# Sheet5_LCD.net
KiCad netlist of a schematic drawn in Altium Designer
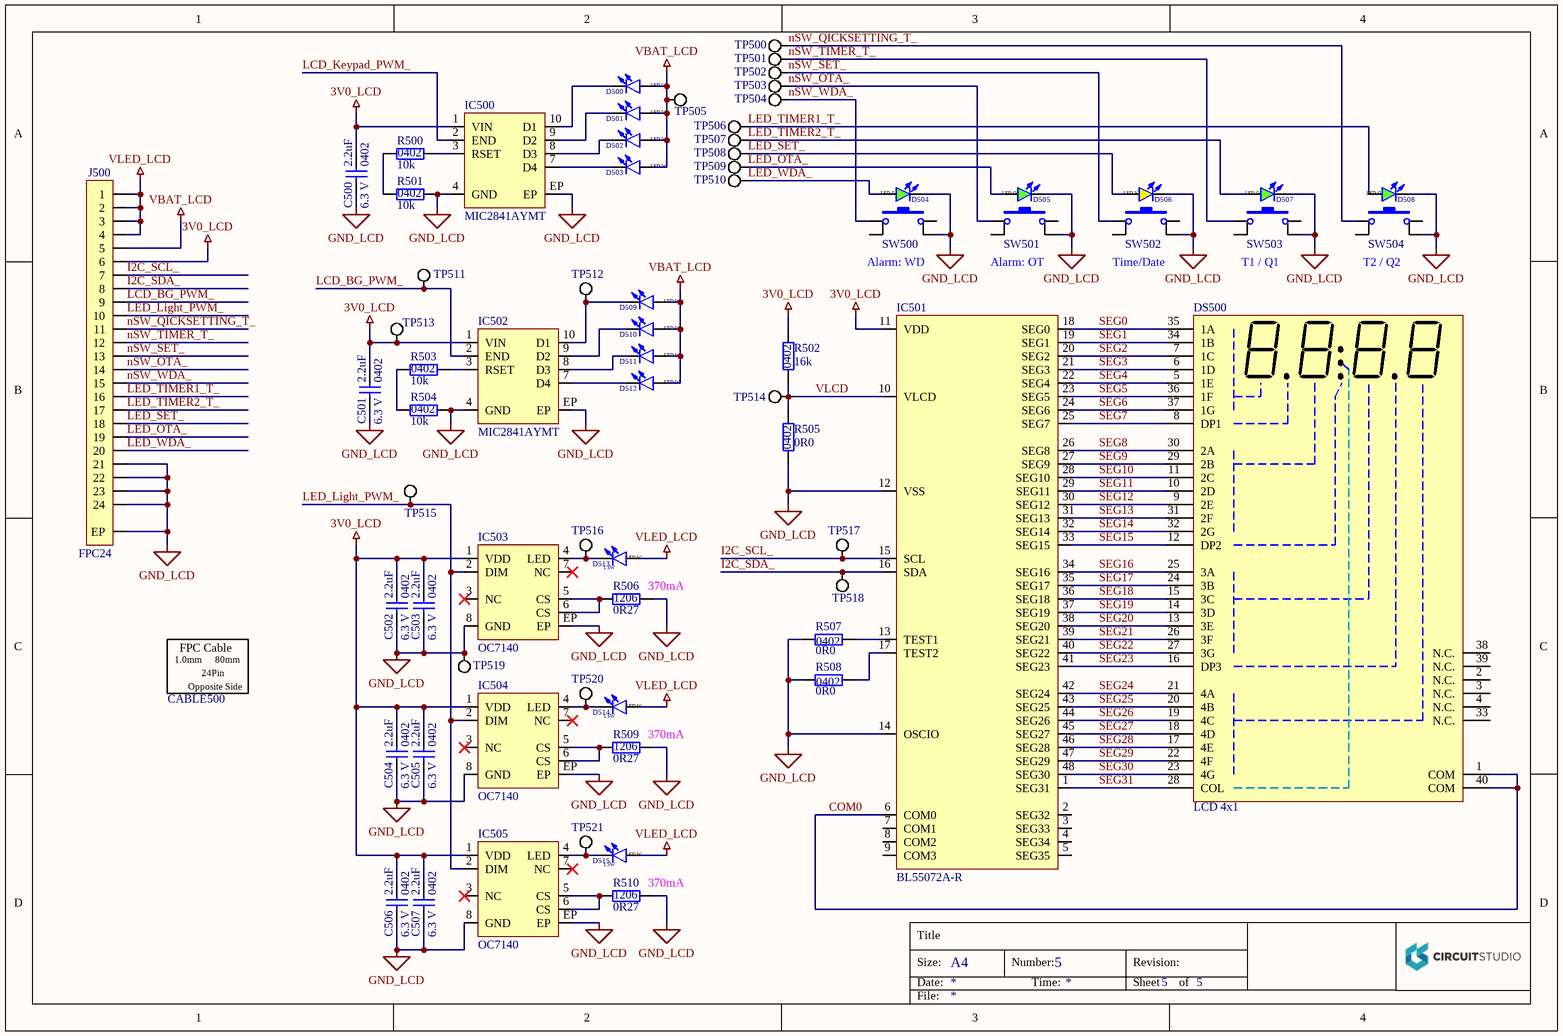
[diagram p0: Sheet5_LCD.SchDoc]

(export (version "E")
  (design (tool "Eeschema 10.0.6"))
  (components
    (comp (ref "C500")
      (value "C 2.2uF 0402 6.3V")
      (footprint "0402")
      (description "CAP CER 2.2UF 6.3V X6T 0402")
      (fields
        (field (name "MANUFACTURER") "Murata Electronics")
        (field (name "MANUFACTURER PART NUMBER") "GRM155D80J225ME95D")
        (field (name "CAPACITANCE") "2.2uF")
        (field (name "VOLTAGE") "6.3 V")
      )
      (libsource (lib "CS_Part_Library") (part "CAP_2.2uF_6V3_0402"))
    )
    (comp (ref "C501")
      (value "C 2.2uF 0402 6.3V")
      (footprint "0402")
      (description "CAP CER 2.2UF 6.3V X6T 0402")
      (fields
        (field (name "MANUFACTURER") "Murata Electronics")
        (field (name "MANUFACTURER PART NUMBER") "GRM155D80J225ME95D")
        (field (name "CAPACITANCE") "2.2uF")
        (field (name "VOLTAGE") "6.3 V")
      )
      (libsource (lib "CS_Part_Library") (part "CAP_2.2uF_6V3_0402"))
    )
    (comp (ref "C502")
      (value "C 2.2uF 0402 6.3V")
      (footprint "0402")
      (description "CAP CER 2.2UF 6.3V X6T 0402")
      (fields
        (field (name "MANUFACTURER") "Murata Electronics")
        (field (name "MANUFACTURER PART NUMBER") "GRM155D80J225ME95D")
        (field (name "CAPACITANCE") "2.2uF")
        (field (name "VOLTAGE") "6.3 V")
      )
      (libsource (lib "CS_Part_Library") (part "CAP_2.2uF_6V3_0402"))
    )
    (comp (ref "C503")
      (value "C 2.2uF 0402 6.3V")
      (footprint "0402")
      (description "CAP CER 2.2UF 6.3V X6T 0402")
      (fields
        (field (name "MANUFACTURER") "Murata Electronics")
        (field (name "MANUFACTURER PART NUMBER") "GRM155D80J225ME95D")
        (field (name "CAPACITANCE") "2.2uF")
        (field (name "VOLTAGE") "6.3 V")
      )
      (libsource (lib "CS_Part_Library") (part "CAP_2.2uF_6V3_0402"))
    )
    (comp (ref "C504")
      (value "C 2.2uF 0402 6.3V")
      (footprint "0402")
      (description "CAP CER 2.2UF 6.3V X6T 0402")
      (fields
        (field (name "MANUFACTURER") "Murata Electronics")
        (field (name "MANUFACTURER PART NUMBER") "GRM155D80J225ME95D")
        (field (name "CAPACITANCE") "2.2uF")
        (field (name "VOLTAGE") "6.3 V")
      )
      (libsource (lib "CS_Part_Library") (part "CAP_2.2uF_6V3_0402"))
    )
    (comp (ref "C505")
      (value "C 2.2uF 0402 6.3V")
      (footprint "0402")
      (description "CAP CER 2.2UF 6.3V X6T 0402")
      (fields
        (field (name "MANUFACTURER") "Murata Electronics")
        (field (name "MANUFACTURER PART NUMBER") "GRM155D80J225ME95D")
        (field (name "CAPACITANCE") "2.2uF")
        (field (name "VOLTAGE") "6.3 V")
      )
      (libsource (lib "CS_Part_Library") (part "CAP_2.2uF_6V3_0402"))
    )
    (comp (ref "C506")
      (value "C 2.2uF 0402 6.3V")
      (footprint "0402")
      (description "CAP CER 2.2UF 6.3V X6T 0402")
      (fields
        (field (name "MANUFACTURER") "Murata Electronics")
        (field (name "MANUFACTURER PART NUMBER") "GRM155D80J225ME95D")
        (field (name "CAPACITANCE") "2.2uF")
        (field (name "VOLTAGE") "6.3 V")
      )
      (libsource (lib "CS_Part_Library") (part "CAP_2.2uF_6V3_0402"))
    )
    (comp (ref "C507")
      (value "C 2.2uF 0402 6.3V")
      (footprint "0402")
      (description "CAP CER 2.2UF 6.3V X6T 0402")
      (fields
        (field (name "MANUFACTURER") "Murata Electronics")
        (field (name "MANUFACTURER PART NUMBER") "GRM155D80J225ME95D")
        (field (name "CAPACITANCE") "2.2uF")
        (field (name "VOLTAGE") "6.3 V")
      )
      (libsource (lib "CS_Part_Library") (part "CAP_2.2uF_6V3_0402"))
    )
    (comp (ref "CABLE500")
      (value "FPC24p80mm")
      (description "FPC Cable 1mm Pitch 24Pin 80mm Opposite Sides")
      (fields
        (field (name "MANUFACTURER") "LX")
        (field (name "MANUFACTURER PART NUMBER") "C50299")
        (field (name "PITCH") "1.0mm")
        (field (name "LENGTH") "80mm")
        (field (name "MODE") "Opposite Side")
        (field (name "NOOFPINS") "24Pin")
      )
      (libsource (lib "Symbols") (part "CABLE_FPC24_80"))
    )
    (comp (ref "D500")
      (value "LED W")
      (footprint "LED_99-218UMC_side")
      (description "LED WHITE SIDE SMD")
      (fields
        (field (name "MANUFACTURER") "Everlight Elec")
        (field (name "MANUFACTURER PART NUMBER") "99-218UMC/1637CD/TR8-T")
      )
      (libsource (lib "Symbols") (part "D_LED_White_s"))
    )
    (comp (ref "D501")
      (value "LED W")
      (footprint "LED_99-218UMC_side")
      (description "LED WHITE SIDE SMD")
      (fields
        (field (name "MANUFACTURER") "Everlight Elec")
        (field (name "MANUFACTURER PART NUMBER") "99-218UMC/1637CD/TR8-T")
      )
      (libsource (lib "Symbols") (part "D_LED_White_s"))
    )
    (comp (ref "D502")
      (value "LED W")
      (footprint "LED_99-218UMC_side")
      (description "LED WHITE SIDE SMD")
      (fields
        (field (name "MANUFACTURER") "Everlight Elec")
        (field (name "MANUFACTURER PART NUMBER") "99-218UMC/1637CD/TR8-T")
      )
      (libsource (lib "Symbols") (part "D_LED_White_s"))
    )
    (comp (ref "D503")
      (value "LED W")
      (footprint "LED_99-218UMC_side")
      (description "LED WHITE SIDE SMD")
      (fields
        (field (name "MANUFACTURER") "Everlight Elec")
        (field (name "MANUFACTURER PART NUMBER") "99-218UMC/1637CD/TR8-T")
      )
      (libsource (lib "Symbols") (part "D_LED_White_s"))
    )
    (comp (ref "D504")
      (value "LED G")
      (footprint "LED_0603")
      (description "LED GREEN DIFFUSED 0603 SMD")
      (fields
        (field (name "MANUFACTURER") "OSRAM Opto Semiconductors Inc.")
        (field (name "MANUFACTURER PART NUMBER") "LT Q39G-Q1OO-25-1")
      )
      (libsource (lib "CS_Part_Library") (part "D_LED_Green_0603"))
    )
    (comp (ref "D505")
      (value "LED G")
      (footprint "LED_0603")
      (description "LED GREEN DIFFUSED 0603 SMD")
      (fields
        (field (name "MANUFACTURER") "OSRAM Opto Semiconductors Inc.")
        (field (name "MANUFACTURER PART NUMBER") "LT Q39G-Q1OO-25-1")
      )
      (libsource (lib "CS_Part_Library") (part "D_LED_Green_0603"))
    )
    (comp (ref "D506")
      (value "LED Y")
      (footprint "LED_0603")
      (description "LED YELLOW DIFFUSED")
      (fields
        (field (name "MANUFACTURER") "Stanley Electric Co")
        (field (name "MANUFACTURER PART NUMBER") "FKY1111C-TR")
      )
      (libsource (lib "CS_Part_Library") (part "D_LED_Yellow_0603"))
    )
    (comp (ref "D507")
      (value "LED G")
      (footprint "LED_0603")
      (description "LED GREEN DIFFUSED 0603 SMD")
      (fields
        (field (name "MANUFACTURER") "OSRAM Opto Semiconductors Inc.")
        (field (name "MANUFACTURER PART NUMBER") "LT Q39G-Q1OO-25-1")
      )
      (libsource (lib "CS_Part_Library") (part "D_LED_Green_0603"))
    )
    (comp (ref "D508")
      (value "LED G")
      (footprint "LED_0603")
      (description "LED GREEN DIFFUSED 0603 SMD")
      (fields
        (field (name "MANUFACTURER") "OSRAM Opto Semiconductors Inc.")
        (field (name "MANUFACTURER PART NUMBER") "LT Q39G-Q1OO-25-1")
      )
      (libsource (lib "CS_Part_Library") (part "D_LED_Green_0603"))
    )
    (comp (ref "D509")
      (value "LED W")
      (footprint "LED_99-218UMC_side")
      (description "LED WHITE SIDE SMD")
      (fields
        (field (name "MANUFACTURER") "Everlight Elec")
        (field (name "MANUFACTURER PART NUMBER") "99-218UMC/1637CD/TR8-T")
      )
      (libsource (lib "Symbols") (part "D_LED_White_s"))
    )
    (comp (ref "D510")
      (value "LED W")
      (footprint "LED_99-218UMC_side")
      (description "LED WHITE SIDE SMD")
      (fields
        (field (name "MANUFACTURER") "Everlight Elec")
        (field (name "MANUFACTURER PART NUMBER") "99-218UMC/1637CD/TR8-T")
      )
      (libsource (lib "Symbols") (part "D_LED_White_s"))
    )
    (comp (ref "D511")
      (value "LED W")
      (footprint "LED_99-218UMC_side")
      (description "LED WHITE SIDE SMD")
      (fields
        (field (name "MANUFACTURER") "Everlight Elec")
        (field (name "MANUFACTURER PART NUMBER") "99-218UMC/1637CD/TR8-T")
      )
      (libsource (lib "Symbols") (part "D_LED_White_s"))
    )
    (comp (ref "D512")
      (value "LED W")
      (footprint "LED_99-218UMC_side")
      (description "LED WHITE SIDE SMD")
      (fields
        (field (name "MANUFACTURER") "Everlight Elec")
        (field (name "MANUFACTURER PART NUMBER") "99-218UMC/1637CD/TR8-T")
      )
      (libsource (lib "Symbols") (part "D_LED_White_s"))
    )
    (comp (ref "D513")
      (value "LED W")
      (footprint "LED_3.5x3.15")
      (description "LED XLAMP WARM WHITE 3250K 4SMD")
      (fields
        (field (name "MANUFACTURER") "CreeLED, Inc.")
        (field (name "MANUFACTURER PART NUMBER") "MLEAWT-A1-0000-0003F7")
        (field (name "POWER") "1.5W")
      )
      (libsource (lib "CS_Part_Library") (part "D_LED_W_HP"))
    )
    (comp (ref "D514")
      (value "LED W")
      (footprint "LED_3.5x3.15")
      (description "LED XLAMP WARM WHITE 3250K 4SMD")
      (fields
        (field (name "MANUFACTURER") "CreeLED, Inc.")
        (field (name "MANUFACTURER PART NUMBER") "MLEAWT-A1-0000-0003F7")
        (field (name "POWER") "1.5W")
      )
      (libsource (lib "CS_Part_Library") (part "D_LED_W_HP"))
    )
    (comp (ref "D515")
      (value "LED W")
      (footprint "LED_3.5x3.15")
      (description "LED XLAMP WARM WHITE 3250K 4SMD")
      (fields
        (field (name "MANUFACTURER") "CreeLED, Inc.")
        (field (name "MANUFACTURER PART NUMBER") "MLEAWT-A1-0000-0003F7")
        (field (name "POWER") "1.5W")
      )
      (libsource (lib "CS_Part_Library") (part "D_LED_W_HP"))
    )
    (comp (ref "DS500")
      (value "LCD 4x1")
      (footprint "DISPL_7SEG_4")
      (description "LCD MOD 4 DIG 4 X 1 REFLECTIVE")
      (fields
        (field (name "MANUFACTURER") "Varitronix")
        (field (name "MANUFACTURER PART NUMBER") "VI-402-DP-RC-S")
      )
      (libsource (lib "Symbols") (part "DISPL_7SEG_4x1"))
    )
    (comp (ref "IC500")
      (value "MIC2841AYMT")
      (footprint "UFDFN-10")
      (description "IC LED DRIVER 4 CH")
      (fields
        (field (name "MANUFACTURER") "Microchip Technology")
        (field (name "MANUFACTURER PART NUMBER") "MIC2841AYMT-TR")
      )
      (libsource (lib "CS_Part_Library") (part "IC_LED_cntr_MIC2841"))
    )
    (comp (ref "IC501")
      (value "BL55072A-R")
      (footprint "TSSOP-48")
      (description "IC LCD DRIVER 36SEG TSSOP-48")
      (fields (field (name "MANUFACTURER") "BL(Shanghai Belling)"))
      (libsource (lib "Symbols") (part "IC_LCD_cntr_BL55072A-R"))
    )
    (comp (ref "IC502")
      (value "MIC2841AYMT")
      (footprint "UFDFN-10")
      (description "IC LED DRIVER 4 CH")
      (fields
        (field (name "MANUFACTURER") "Microchip Technology")
        (field (name "MANUFACTURER PART NUMBER") "MIC2841AYMT-TR")
      )
      (libsource (lib "CS_Part_Library") (part "IC_LED_cntr_MIC2841"))
    )
    (comp (ref "IC503")
      (value "OC7140")
      (footprint "SOIC-8-EP")
      (description "IC LED DRIVER 1 CH 2A ESOP8")
      (fields (field (name "MANUFACTURER") "OCX"))
      (libsource (lib "Symbols") (part "IC_LED_cntr_OC7140"))
    )
    (comp (ref "IC504")
      (value "OC7140")
      (footprint "SOIC-8-EP")
      (description "IC LED DRIVER 1 CH 2A ESOP8")
      (fields (field (name "MANUFACTURER") "OCX"))
      (libsource (lib "Symbols") (part "IC_LED_cntr_OC7140"))
    )
    (comp (ref "IC505")
      (value "OC7140")
      (footprint "SOIC-8-EP")
      (description "IC LED DRIVER 1 CH 2A ESOP8")
      (fields (field (name "MANUFACTURER") "OCX"))
      (libsource (lib "Symbols") (part "IC_LED_cntr_OC7140"))
    )
    (comp (ref "J500")
      (value "FPC24")
      (footprint "J_FPC_522712479")
      (description "CONN FPC BOT 24 PIN 1mm Pitch")
      (fields (field (name "MANUFACTURER") "MOLEX") (field (name "MANUFACTURER PART NUMBER") "522712479"))
      (libsource (lib "Symbols") (part "J_FPC24_DS"))
    )
    (comp (ref "R500")
      (value "R 10k 0402")
      (footprint "0402")
      (description "RES 10K OHM 1% 1/16W 0402")
      (fields
        (field (name "MANUFACTURER") "YAGEO")
        (field (name "MANUFACTURER PART NUMBER") "RC0402FR-0710KL")
        (field (name "RESISTANCE") "10k")
      )
      (libsource (lib "CS_Part_Library") (part "R_10k_0402"))
    )
    (comp (ref "R501")
      (value "R 10k 0402")
      (footprint "0402")
      (description "RES 10K OHM 1% 1/16W 0402")
      (fields
        (field (name "MANUFACTURER") "YAGEO")
        (field (name "MANUFACTURER PART NUMBER") "RC0402FR-0710KL")
        (field (name "RESISTANCE") "10k")
      )
      (libsource (lib "CS_Part_Library") (part "R_10k_0402"))
    )
    (comp (ref "R502")
      (value "R 16k 0402")
      (footprint "0402")
      (description "RES 16K OHM 1% 1/16W 0402")
      (fields
        (field (name "MANUFACTURER") "Stackpole Electronics Inc")
        (field (name "MANUFACTURER PART NUMBER") "RMCF0402FT16K0")
        (field (name "RESISTANCE") "16k")
      )
      (libsource (lib "CS_Part_Library") (part "R_16k_0402"))
    )
    (comp (ref "R503")
      (value "R 10k 0402")
      (footprint "0402")
      (description "RES 10K OHM 1% 1/16W 0402")
      (fields
        (field (name "MANUFACTURER") "YAGEO")
        (field (name "MANUFACTURER PART NUMBER") "RC0402FR-0710KL")
        (field (name "RESISTANCE") "10k")
      )
      (libsource (lib "CS_Part_Library") (part "R_10k_0402"))
    )
    (comp (ref "R504")
      (value "R 10k 0402")
      (footprint "0402")
      (description "RES 10K OHM 1% 1/16W 0402")
      (fields
        (field (name "MANUFACTURER") "YAGEO")
        (field (name "MANUFACTURER PART NUMBER") "RC0402FR-0710KL")
        (field (name "RESISTANCE") "10k")
      )
      (libsource (lib "CS_Part_Library") (part "R_10k_0402"))
    )
    (comp (ref "R505")
      (value "R 0R0 0402")
      (footprint "0402")
      (description "RES 0 OHM JUMPER 1/16W 0402")
      (fields
        (field (name "MANUFACTURER") "Stackpole Electronics Inc")
        (field (name "MANUFACTURER PART NUMBER") "RMCF0402ZT0R00")
        (field (name "RESISTANCE") "0R0")
      )
      (libsource (lib "") (part "R_0R0_0402_1"))
    )
    (comp (ref "R506")
      (value "R 0R27 1206")
      (footprint "1206")
      (description "RES 0.27 OHM 1% 1/3W 1206")
      (fields
        (field (name "MANUFACTURER") "RALEC")
        (field (name "MANUFACTURER PART NUMBER") "RTT06R270FTP")
        (field (name "RESISTANCE") "0R27")
      )
      (libsource (lib "Symbols") (part "R_0R27_1206"))
    )
    (comp (ref "R507")
      (value "R 0R0 0402")
      (footprint "0402")
      (description "RES 0 OHM JUMPER 1/16W 0402")
      (fields
        (field (name "MANUFACTURER") "Stackpole Electronics Inc")
        (field (name "MANUFACTURER PART NUMBER") "RMCF0402ZT0R00")
        (field (name "RESISTANCE") "0R0")
      )
      (libsource (lib "CS_Part_Library") (part "R_0R0_0402"))
    )
    (comp (ref "R508")
      (value "R 0R0 0402")
      (footprint "0402")
      (description "RES 0 OHM JUMPER 1/16W 0402")
      (fields
        (field (name "MANUFACTURER") "Stackpole Electronics Inc")
        (field (name "MANUFACTURER PART NUMBER") "RMCF0402ZT0R00")
        (field (name "RESISTANCE") "0R0")
      )
      (libsource (lib "CS_Part_Library") (part "R_0R0_0402"))
    )
    (comp (ref "R509")
      (value "R 0R27 1206")
      (footprint "1206")
      (description "RES 0.27 OHM 1% 1/3W 1206")
      (fields
        (field (name "MANUFACTURER") "RALEC")
        (field (name "MANUFACTURER PART NUMBER") "RTT06R270FTP")
        (field (name "RESISTANCE") "0R27")
      )
      (libsource (lib "Symbols") (part "R_0R27_1206"))
    )
    (comp (ref "R510")
      (value "R 0R27 1206")
      (footprint "1206")
      (description "RES 0.27 OHM 1% 1/3W 1206")
      (fields
        (field (name "MANUFACTURER") "RALEC")
        (field (name "MANUFACTURER PART NUMBER") "RTT06R270FTP")
        (field (name "RESISTANCE") "0R27")
      )
      (libsource (lib "Symbols") (part "R_0R27_1206"))
    )
    (comp (ref "SW500")
      (value "SW")
      (footprint "SW_BRIGHT_6.1x6.1")
      (description "SWITCH TACTILE SW-SMD")
      (fields
        (field (name "MANUFACTURER") "BRIGHT")
        (field (name "MANUFACTURER PART NUMBER") "TSA063G50-250")
      )
      (libsource (lib "CS_Part_Library") (part "SW_TactileSW_V_2"))
    )
    (comp (ref "SW501")
      (value "SW")
      (footprint "SW_BRIGHT_6.1x6.1")
      (description "SWITCH TACTILE SW-SMD")
      (fields
        (field (name "MANUFACTURER") "BRIGHT")
        (field (name "MANUFACTURER PART NUMBER") "TSA063G50-250")
      )
      (libsource (lib "CS_Part_Library") (part "SW_TactileSW_V_2"))
    )
    (comp (ref "SW502")
      (value "SW")
      (footprint "SW_BRIGHT_6.1x6.1")
      (description "SWITCH TACTILE SW-SMD")
      (fields
        (field (name "MANUFACTURER") "BRIGHT")
        (field (name "MANUFACTURER PART NUMBER") "TSA063G50-250")
      )
      (libsource (lib "CS_Part_Library") (part "SW_TactileSW_V_2"))
    )
    (comp (ref "SW503")
      (value "SW")
      (footprint "SW_BRIGHT_6.1x6.1")
      (description "SWITCH TACTILE SW-SMD")
      (fields
        (field (name "MANUFACTURER") "BRIGHT")
        (field (name "MANUFACTURER PART NUMBER") "TSA063G50-250")
      )
      (libsource (lib "CS_Part_Library") (part "SW_TactileSW_V_2"))
    )
    (comp (ref "SW504")
      (value "SW")
      (footprint "SW_BRIGHT_6.1x6.1")
      (description "SWITCH TACTILE SW-SMD")
      (fields
        (field (name "MANUFACTURER") "BRIGHT")
        (field (name "MANUFACTURER PART NUMBER") "TSA063G50-250")
      )
      (libsource (lib "CS_Part_Library") (part "SW_TactileSW_V_2"))
    )
    (comp (ref "TP500")
      (value "TP")
      (footprint "TP_1mm")
      (description "Test Point 1mm")
      (libsource (lib "CS_Part_Library") (part "TP_1mm"))
    )
    (comp (ref "TP501")
      (value "TP")
      (footprint "TP_1mm")
      (description "Test Point 1mm")
      (libsource (lib "CS_Part_Library") (part "TP_1mm"))
    )
    (comp (ref "TP502")
      (value "TP")
      (footprint "TP_1mm")
      (description "Test Point 1mm")
      (libsource (lib "CS_Part_Library") (part "TP_1mm"))
    )
    (comp (ref "TP503")
      (value "TP")
      (footprint "TP_1mm")
      (description "Test Point 1mm")
      (libsource (lib "CS_Part_Library") (part "TP_1mm"))
    )
    (comp (ref "TP504")
      (value "TP")
      (footprint "TP_1mm")
      (description "Test Point 1mm")
      (libsource (lib "CS_Part_Library") (part "TP_1mm"))
    )
    (comp (ref "TP505")
      (value "TP")
      (footprint "TP_1mm")
      (description "Test Point 1mm")
      (libsource (lib "CS_Part_Library") (part "TP_1mm"))
    )
    (comp (ref "TP506")
      (value "TP")
      (footprint "TP_1mm")
      (description "Test Point 1mm")
      (libsource (lib "CS_Part_Library") (part "TP_1mm"))
    )
    (comp (ref "TP507")
      (value "TP")
      (footprint "TP_1mm")
      (description "Test Point 1mm")
      (libsource (lib "CS_Part_Library") (part "TP_1mm"))
    )
    (comp (ref "TP508")
      (value "TP")
      (footprint "TP_1mm")
      (description "Test Point 1mm")
      (libsource (lib "CS_Part_Library") (part "TP_1mm"))
    )
    (comp (ref "TP509")
      (value "TP")
      (footprint "TP_1mm")
      (description "Test Point 1mm")
      (libsource (lib "CS_Part_Library") (part "TP_1mm"))
    )
    (comp (ref "TP510")
      (value "TP")
      (footprint "TP_1mm")
      (description "Test Point 1mm")
      (libsource (lib "CS_Part_Library") (part "TP_1mm"))
    )
    (comp (ref "TP511")
      (value "TP")
      (footprint "TP_1mm")
      (description "Test Point 1mm")
      (libsource (lib "CS_Part_Library") (part "TP_1mm"))
    )
    (comp (ref "TP512")
      (value "TP")
      (footprint "TP_1mm")
      (description "Test Point 1mm")
      (libsource (lib "CS_Part_Library") (part "TP_1mm"))
    )
    (comp (ref "TP513")
      (value "TP")
      (footprint "TP_1mm")
      (description "Test Point 1mm")
      (libsource (lib "CS_Part_Library") (part "TP_1mm"))
    )
    (comp (ref "TP514")
      (value "TP")
      (footprint "TP_1mm")
      (description "Test Point 1mm")
      (libsource (lib "CS_Part_Library") (part "TP_1mm"))
    )
    (comp (ref "TP515")
      (value "TP")
      (footprint "TP_1mm")
      (description "Test Point 1mm")
      (libsource (lib "CS_Part_Library") (part "TP_1mm"))
    )
    (comp (ref "TP516")
      (value "TP")
      (footprint "TP_1mm")
      (description "Test Point 1mm")
      (libsource (lib "CS_Part_Library") (part "TP_1mm"))
    )
    (comp (ref "TP517")
      (value "TP")
      (footprint "TP_1mm")
      (description "Test Point 1mm")
      (libsource (lib "CS_Part_Library") (part "TP_1mm"))
    )
    (comp (ref "TP518")
      (value "TP")
      (footprint "TP_1mm")
      (description "Test Point 1mm")
      (libsource (lib "CS_Part_Library") (part "TP_1mm"))
    )
    (comp (ref "TP519")
      (value "TP")
      (footprint "TP_1mm")
      (description "Test Point 1mm")
      (libsource (lib "CS_Part_Library") (part "TP_1mm"))
    )
    (comp (ref "TP520")
      (value "TP")
      (footprint "TP_1mm")
      (description "Test Point 1mm")
      (libsource (lib "CS_Part_Library") (part "TP_1mm"))
    )
    (comp (ref "TP521")
      (value "TP")
      (footprint "TP_1mm")
      (description "Test Point 1mm")
      (libsource (lib "CS_Part_Library") (part "TP_1mm"))
    )
  )
  (nets
    (net (code "1") (name "/COM0") (class "Default")
      (node (ref "DS500") (pin "1") (pinfunction "COM_1") (pintype "passive"))
      (node (ref "DS500") (pin "40") (pinfunction "COM_40") (pintype "passive"))
      (node (ref "IC501") (pin "6") (pinfunction "COM0_6") (pintype "passive"))
    )
    (net (code "2") (name "/I2C_SCL_") (class "Default")
      (node (ref "IC501") (pin "15") (pinfunction "SCL_15") (pintype "passive"))
      (node (ref "J500") (pin "7") (pinfunction "7_7") (pintype "passive"))
      (node (ref "TP517") (pin "1") (pinfunction "TP_1") (pintype "passive"))
    )
    (net (code "3") (name "/I2C_SDA_") (class "Default")
      (node (ref "IC501") (pin "16") (pinfunction "SDA_16") (pintype "passive"))
      (node (ref "J500") (pin "8") (pinfunction "8_8") (pintype "passive"))
      (node (ref "TP518") (pin "1") (pinfunction "TP_1") (pintype "passive"))
    )
    (net (code "4") (name "/LCD_BG_PWM_") (class "Default")
      (node (ref "IC502") (pin "2") (pinfunction "END_2") (pintype "passive"))
      (node (ref "J500") (pin "9") (pinfunction "9_9") (pintype "passive"))
      (node (ref "TP511") (pin "1") (pinfunction "TP_1") (pintype "passive"))
    )
    (net (code "5") (name "/LCD_Keypad_PWM_") (class "Default")
      (node (ref "IC500") (pin "2") (pinfunction "END_2") (pintype "passive"))
    )
    (net (code "6") (name "/LED_Light_PWM_") (class "Default")
      (node (ref "IC503") (pin "2") (pinfunction "DIM_2") (pintype "passive"))
      (node (ref "IC504") (pin "2") (pinfunction "DIM_2") (pintype "passive"))
      (node (ref "IC505") (pin "2") (pinfunction "DIM_2") (pintype "passive"))
      (node (ref "J500") (pin "10") (pinfunction "10_10") (pintype "passive"))
      (node (ref "TP515") (pin "1") (pinfunction "TP_1") (pintype "passive"))
    )
    (net (code "7") (name "/LED_OTA_") (class "Default")
      (node (ref "D505") (pin "A") (pinfunction "A_A") (pintype "passive"))
      (node (ref "J500") (pin "19") (pinfunction "19_19") (pintype "passive"))
      (node (ref "TP509") (pin "1") (pinfunction "TP_1") (pintype "passive"))
    )
    (net (code "8") (name "/LED_SET_") (class "Default")
      (node (ref "D506") (pin "A") (pinfunction "A_A") (pintype "passive"))
      (node (ref "J500") (pin "18") (pinfunction "18_18") (pintype "passive"))
      (node (ref "TP508") (pin "1") (pinfunction "TP_1") (pintype "passive"))
    )
    (net (code "9") (name "/LED_TIMER1_T_") (class "Default")
      (node (ref "D508") (pin "A") (pinfunction "A_A") (pintype "passive"))
      (node (ref "J500") (pin "16") (pinfunction "16_16") (pintype "passive"))
      (node (ref "TP506") (pin "1") (pinfunction "TP_1") (pintype "passive"))
    )
    (net (code "10") (name "/LED_TIMER2_T_") (class "Default")
      (node (ref "D507") (pin "A") (pinfunction "A_A") (pintype "passive"))
      (node (ref "J500") (pin "17") (pinfunction "17_17") (pintype "passive"))
      (node (ref "TP507") (pin "1") (pinfunction "TP_1") (pintype "passive"))
    )
    (net (code "11") (name "/LED_WDA_") (class "Default")
      (node (ref "D504") (pin "A") (pinfunction "A_A") (pintype "passive"))
      (node (ref "J500") (pin "20") (pinfunction "20_20") (pintype "passive"))
      (node (ref "TP510") (pin "1") (pinfunction "TP_1") (pintype "passive"))
    )
    (net (code "12") (name "/SEG0") (class "Default")
      (node (ref "DS500") (pin "35") (pinfunction "1A_35") (pintype "passive"))
      (node (ref "IC501") (pin "18") (pinfunction "SEG0_18") (pintype "passive"))
    )
    (net (code "13") (name "/SEG1") (class "Default")
      (node (ref "DS500") (pin "34") (pinfunction "1B_34") (pintype "passive"))
      (node (ref "IC501") (pin "19") (pinfunction "SEG1_19") (pintype "passive"))
    )
    (net (code "14") (name "/SEG2") (class "Default")
      (node (ref "DS500") (pin "7") (pinfunction "1C_7") (pintype "passive"))
      (node (ref "IC501") (pin "20") (pinfunction "SEG2_20") (pintype "passive"))
    )
    (net (code "15") (name "/SEG3") (class "Default")
      (node (ref "DS500") (pin "6") (pinfunction "1D_6") (pintype "passive"))
      (node (ref "IC501") (pin "21") (pinfunction "SEG3_21") (pintype "passive"))
    )
    (net (code "16") (name "/SEG4") (class "Default")
      (node (ref "DS500") (pin "5") (pinfunction "1E_5") (pintype "passive"))
      (node (ref "IC501") (pin "22") (pinfunction "SEG4_22") (pintype "passive"))
    )
    (net (code "17") (name "/SEG5") (class "Default")
      (node (ref "DS500") (pin "36") (pinfunction "1F_36") (pintype "passive"))
      (node (ref "IC501") (pin "23") (pinfunction "SEG5_23") (pintype "passive"))
    )
    (net (code "18") (name "/SEG6") (class "Default")
      (node (ref "DS500") (pin "37") (pinfunction "1G_37") (pintype "passive"))
      (node (ref "IC501") (pin "24") (pinfunction "SEG6_24") (pintype "passive"))
    )
    (net (code "19") (name "/SEG7") (class "Default")
      (node (ref "DS500") (pin "8") (pinfunction "DP1_8") (pintype "passive"))
      (node (ref "IC501") (pin "25") (pinfunction "SEG7_25") (pintype "passive"))
    )
    (net (code "20") (name "/SEG8") (class "Default")
      (node (ref "DS500") (pin "30") (pinfunction "2A_30") (pintype "passive"))
      (node (ref "IC501") (pin "26") (pinfunction "SEG8_26") (pintype "passive"))
    )
    (net (code "21") (name "/SEG9") (class "Default")
      (node (ref "DS500") (pin "29") (pinfunction "2B_29") (pintype "passive"))
      (node (ref "IC501") (pin "27") (pinfunction "SEG9_27") (pintype "passive"))
    )
    (net (code "22") (name "/SEG10") (class "Default")
      (node (ref "DS500") (pin "11") (pinfunction "2C_11") (pintype "passive"))
      (node (ref "IC501") (pin "28") (pinfunction "SEG10_28") (pintype "passive"))
    )
    (net (code "23") (name "/SEG11") (class "Default")
      (node (ref "DS500") (pin "10") (pinfunction "2D_10") (pintype "passive"))
      (node (ref "IC501") (pin "29") (pinfunction "SEG11_29") (pintype "passive"))
    )
    (net (code "24") (name "/SEG12") (class "Default")
      (node (ref "DS500") (pin "9") (pinfunction "2E_9") (pintype "passive"))
      (node (ref "IC501") (pin "30") (pinfunction "SEG12_30") (pintype "passive"))
    )
    (net (code "25") (name "/SEG13") (class "Default")
      (node (ref "DS500") (pin "31") (pinfunction "2F_31") (pintype "passive"))
      (node (ref "IC501") (pin "31") (pinfunction "SEG13_31") (pintype "passive"))
    )
    (net (code "26") (name "/SEG14") (class "Default")
      (node (ref "DS500") (pin "32") (pinfunction "2G_32") (pintype "passive"))
      (node (ref "IC501") (pin "32") (pinfunction "SEG14_32") (pintype "passive"))
    )
    (net (code "27") (name "/SEG15") (class "Default")
      (node (ref "DS500") (pin "12") (pinfunction "DP2_12") (pintype "passive"))
      (node (ref "IC501") (pin "33") (pinfunction "SEG15_33") (pintype "passive"))
    )
    (net (code "28") (name "/SEG16") (class "Default")
      (node (ref "DS500") (pin "25") (pinfunction "3A_25") (pintype "passive"))
      (node (ref "IC501") (pin "34") (pinfunction "SEG16_34") (pintype "passive"))
    )
    (net (code "29") (name "/SEG17") (class "Default")
      (node (ref "DS500") (pin "24") (pinfunction "3B_24") (pintype "passive"))
      (node (ref "IC501") (pin "35") (pinfunction "SEG17_35") (pintype "passive"))
    )
    (net (code "30") (name "/SEG18") (class "Default")
      (node (ref "DS500") (pin "15") (pinfunction "3C_15") (pintype "passive"))
      (node (ref "IC501") (pin "36") (pinfunction "SEG18_36") (pintype "passive"))
    )
    (net (code "31") (name "/SEG19") (class "Default")
      (node (ref "DS500") (pin "14") (pinfunction "3D_14") (pintype "passive"))
      (node (ref "IC501") (pin "37") (pinfunction "SEG19_37") (pintype "passive"))
    )
    (net (code "32") (name "/SEG20") (class "Default")
      (node (ref "DS500") (pin "13") (pinfunction "3E_13") (pintype "passive"))
      (node (ref "IC501") (pin "38") (pinfunction "SEG20_38") (pintype "passive"))
    )
    (net (code "33") (name "/SEG21") (class "Default")
      (node (ref "DS500") (pin "26") (pinfunction "3F_26") (pintype "passive"))
      (node (ref "IC501") (pin "39") (pinfunction "SEG21_39") (pintype "passive"))
    )
    (net (code "34") (name "/SEG22") (class "Default")
      (node (ref "DS500") (pin "27") (pinfunction "3G_27") (pintype "passive"))
      (node (ref "IC501") (pin "40") (pinfunction "SEG22_40") (pintype "passive"))
    )
    (net (code "35") (name "/SEG23") (class "Default")
      (node (ref "DS500") (pin "16") (pinfunction "DP3_16") (pintype "passive"))
      (node (ref "IC501") (pin "41") (pinfunction "SEG23_41") (pintype "passive"))
    )
    (net (code "36") (name "/SEG24") (class "Default")
      (node (ref "DS500") (pin "21") (pinfunction "4A_21") (pintype "passive"))
      (node (ref "IC501") (pin "42") (pinfunction "SEG24_42") (pintype "passive"))
    )
    (net (code "37") (name "/SEG25") (class "Default")
      (node (ref "DS500") (pin "20") (pinfunction "4B_20") (pintype "passive"))
      (node (ref "IC501") (pin "43") (pinfunction "SEG25_43") (pintype "passive"))
    )
    (net (code "38") (name "/SEG26") (class "Default")
      (node (ref "DS500") (pin "19") (pinfunction "4C_19") (pintype "passive"))
      (node (ref "IC501") (pin "44") (pinfunction "SEG26_44") (pintype "passive"))
    )
    (net (code "39") (name "/SEG27") (class "Default")
      (node (ref "DS500") (pin "18") (pinfunction "4D_18") (pintype "passive"))
      (node (ref "IC501") (pin "45") (pinfunction "SEG27_45") (pintype "passive"))
    )
    (net (code "40") (name "/SEG28") (class "Default")
      (node (ref "DS500") (pin "17") (pinfunction "4E_17") (pintype "passive"))
      (node (ref "IC501") (pin "46") (pinfunction "SEG28_46") (pintype "passive"))
    )
    (net (code "41") (name "/SEG29") (class "Default")
      (node (ref "DS500") (pin "22") (pinfunction "4F_22") (pintype "passive"))
      (node (ref "IC501") (pin "47") (pinfunction "SEG29_47") (pintype "passive"))
    )
    (net (code "42") (name "/SEG30") (class "Default")
      (node (ref "DS500") (pin "23") (pinfunction "4G_23") (pintype "passive"))
      (node (ref "IC501") (pin "48") (pinfunction "SEG30_48") (pintype "passive"))
    )
    (net (code "43") (name "/SEG31") (class "Default")
      (node (ref "DS500") (pin "28") (pinfunction "COL_28") (pintype "passive"))
      (node (ref "IC501") (pin "1") (pinfunction "SEG31_1") (pintype "passive"))
    )
    (net (code "44") (name "/VLCD") (class "Default")
      (node (ref "IC501") (pin "10") (pinfunction "VLCD_10") (pintype "passive"))
      (node (ref "R502") (pin "1") (pinfunction "1_1") (pintype "passive"))
      (node (ref "R505") (pin "2") (pinfunction "2_2") (pintype "passive"))
      (node (ref "TP514") (pin "1") (pinfunction "TP_1") (pintype "passive"))
    )
    (net (code "45") (name "/nSW_OTA_") (class "Default")
      (node (ref "J500") (pin "14") (pinfunction "14_14") (pintype "passive"))
      (node (ref "SW501") (pin "1") (pinfunction "1_1") (pintype "passive"))
      (node (ref "TP503") (pin "1") (pinfunction "TP_1") (pintype "passive"))
    )
    (net (code "46") (name "/nSW_QICKSETTING_T_") (class "Default")
      (node (ref "J500") (pin "11") (pinfunction "11_11") (pintype "passive"))
      (node (ref "SW504") (pin "1") (pinfunction "1_1") (pintype "passive"))
      (node (ref "TP500") (pin "1") (pinfunction "TP_1") (pintype "passive"))
    )
    (net (code "47") (name "/nSW_SET_") (class "Default")
      (node (ref "J500") (pin "13") (pinfunction "13_13") (pintype "passive"))
      (node (ref "SW502") (pin "1") (pinfunction "1_1") (pintype "passive"))
      (node (ref "TP502") (pin "1") (pinfunction "TP_1") (pintype "passive"))
    )
    (net (code "48") (name "/nSW_TIMER_T_") (class "Default")
      (node (ref "J500") (pin "12") (pinfunction "12_12") (pintype "passive"))
      (node (ref "SW503") (pin "1") (pinfunction "1_1") (pintype "passive"))
      (node (ref "TP501") (pin "1") (pinfunction "TP_1") (pintype "passive"))
    )
    (net (code "49") (name "/nSW_WDA_") (class "Default")
      (node (ref "J500") (pin "15") (pinfunction "15_15") (pintype "passive"))
      (node (ref "SW500") (pin "1") (pinfunction "1_1") (pintype "passive"))
      (node (ref "TP504") (pin "1") (pinfunction "TP_1") (pintype "passive"))
    )
    (net (code "50") (name "3V0_LCD") (class "Default")
      (node (ref "C500") (pin "2") (pinfunction "2_2") (pintype "passive"))
      (node (ref "C501") (pin "2") (pinfunction "2_2") (pintype "passive"))
      (node (ref "C502") (pin "2") (pinfunction "2_2") (pintype "passive"))
      (node (ref "C503") (pin "2") (pinfunction "2_2") (pintype "passive"))
      (node (ref "C504") (pin "2") (pinfunction "2_2") (pintype "passive"))
      (node (ref "C505") (pin "2") (pinfunction "2_2") (pintype "passive"))
      (node (ref "C506") (pin "2") (pinfunction "2_2") (pintype "passive"))
      (node (ref "C507") (pin "2") (pinfunction "2_2") (pintype "passive"))
      (node (ref "IC500") (pin "1") (pinfunction "VIN_1") (pintype "passive"))
      (node (ref "IC501") (pin "11") (pinfunction "VDD_11") (pintype "passive"))
      (node (ref "IC502") (pin "1") (pinfunction "VIN_1") (pintype "passive"))
      (node (ref "IC503") (pin "1") (pinfunction "VDD_1") (pintype "passive"))
      (node (ref "IC504") (pin "1") (pinfunction "VDD_1") (pintype "passive"))
      (node (ref "IC505") (pin "1") (pinfunction "VDD_1") (pintype "passive"))
      (node (ref "J500") (pin "6") (pinfunction "6_6") (pintype "passive"))
      (node (ref "R502") (pin "2") (pinfunction "2_2") (pintype "passive"))
      (node (ref "TP513") (pin "1") (pinfunction "TP_1") (pintype "passive"))
    )
    (net (code "51") (name "GND_LCD") (class "Default")
      (node (ref "C500") (pin "1") (pinfunction "1_1") (pintype "passive"))
      (node (ref "C501") (pin "1") (pinfunction "1_1") (pintype "passive"))
      (node (ref "C502") (pin "1") (pinfunction "1_1") (pintype "passive"))
      (node (ref "C503") (pin "1") (pinfunction "1_1") (pintype "passive"))
      (node (ref "C504") (pin "1") (pinfunction "1_1") (pintype "passive"))
      (node (ref "C505") (pin "1") (pinfunction "1_1") (pintype "passive"))
      (node (ref "C506") (pin "1") (pinfunction "1_1") (pintype "passive"))
      (node (ref "C507") (pin "1") (pinfunction "1_1") (pintype "passive"))
      (node (ref "D504") (pin "K") (pinfunction "K_K") (pintype "passive"))
      (node (ref "D505") (pin "K") (pinfunction "K_K") (pintype "passive"))
      (node (ref "D506") (pin "K") (pinfunction "K_K") (pintype "passive"))
      (node (ref "D507") (pin "K") (pinfunction "K_K") (pintype "passive"))
      (node (ref "D508") (pin "K") (pinfunction "K_K") (pintype "passive"))
      (node (ref "IC500") (pin "4") (pinfunction "GND_4") (pintype "passive"))
      (node (ref "IC500") (pin "EP") (pinfunction "EP_EP") (pintype "passive"))
      (node (ref "IC501") (pin "12") (pinfunction "VSS_12") (pintype "passive"))
      (node (ref "IC501") (pin "14") (pinfunction "OSCIO_14") (pintype "passive"))
      (node (ref "IC502") (pin "4") (pinfunction "GND_4") (pintype "passive"))
      (node (ref "IC502") (pin "EP") (pinfunction "EP_EP") (pintype "passive"))
      (node (ref "IC503") (pin "8") (pinfunction "GND_8") (pintype "passive"))
      (node (ref "IC503") (pin "EP") (pinfunction "EP_EP") (pintype "passive"))
      (node (ref "IC504") (pin "8") (pinfunction "GND_8") (pintype "passive"))
      (node (ref "IC504") (pin "EP") (pinfunction "EP_EP") (pintype "passive"))
      (node (ref "IC505") (pin "8") (pinfunction "GND_8") (pintype "passive"))
      (node (ref "IC505") (pin "EP") (pinfunction "EP_EP") (pintype "passive"))
      (node (ref "J500") (pin "21") (pinfunction "21_21") (pintype "passive"))
      (node (ref "J500") (pin "22") (pinfunction "22_22") (pintype "passive"))
      (node (ref "J500") (pin "23") (pinfunction "23_23") (pintype "passive"))
      (node (ref "J500") (pin "24") (pinfunction "24_24") (pintype "passive"))
      (node (ref "J500") (pin "EP") (pinfunction "EP_EP") (pintype "passive"))
      (node (ref "R501") (pin "1") (pinfunction "1_1") (pintype "passive"))
      (node (ref "R504") (pin "1") (pinfunction "1_1") (pintype "passive"))
      (node (ref "R505") (pin "1") (pinfunction "1_1") (pintype "passive"))
      (node (ref "R506") (pin "2") (pinfunction "2_2") (pintype "passive"))
      (node (ref "R507") (pin "2") (pinfunction "2_2") (pintype "passive"))
      (node (ref "R508") (pin "2") (pinfunction "2_2") (pintype "passive"))
      (node (ref "R509") (pin "2") (pinfunction "2_2") (pintype "passive"))
      (node (ref "R510") (pin "2") (pinfunction "2_2") (pintype "passive"))
      (node (ref "SW500") (pin "4") (pinfunction "4_4") (pintype "passive"))
      (node (ref "SW501") (pin "4") (pinfunction "4_4") (pintype "passive"))
      (node (ref "SW502") (pin "4") (pinfunction "4_4") (pintype "passive"))
      (node (ref "SW503") (pin "4") (pinfunction "4_4") (pintype "passive"))
      (node (ref "SW504") (pin "4") (pinfunction "4_4") (pintype "passive"))
      (node (ref "TP519") (pin "1") (pinfunction "TP_1") (pintype "passive"))
    )
    (net (code "52") (name "Net-(D500-K)") (class "Default")
      (node (ref "D500") (pin "1") (pinfunction "K_1") (pintype "passive"))
      (node (ref "IC500") (pin "10") (pinfunction "D1_10") (pintype "passive"))
    )
    (net (code "53") (name "Net-(D501-K)") (class "Default")
      (node (ref "D501") (pin "1") (pinfunction "K_1") (pintype "passive"))
      (node (ref "IC500") (pin "9") (pinfunction "D2_9") (pintype "passive"))
    )
    (net (code "54") (name "Net-(D502-K)") (class "Default")
      (node (ref "D502") (pin "1") (pinfunction "K_1") (pintype "passive"))
      (node (ref "IC500") (pin "8") (pinfunction "D3_8") (pintype "passive"))
    )
    (net (code "55") (name "Net-(D503-K)") (class "Default")
      (node (ref "D503") (pin "1") (pinfunction "K_1") (pintype "passive"))
      (node (ref "IC500") (pin "7") (pinfunction "D4_7") (pintype "passive"))
    )
    (net (code "56") (name "Net-(D509-K)") (class "Default")
      (node (ref "D509") (pin "1") (pinfunction "K_1") (pintype "passive"))
      (node (ref "IC502") (pin "10") (pinfunction "D1_10") (pintype "passive"))
      (node (ref "TP512") (pin "1") (pinfunction "TP_1") (pintype "passive"))
    )
    (net (code "57") (name "Net-(D510-K)") (class "Default")
      (node (ref "D510") (pin "1") (pinfunction "K_1") (pintype "passive"))
      (node (ref "IC502") (pin "9") (pinfunction "D2_9") (pintype "passive"))
    )
    (net (code "58") (name "Net-(D511-K)") (class "Default")
      (node (ref "D511") (pin "1") (pinfunction "K_1") (pintype "passive"))
      (node (ref "IC502") (pin "8") (pinfunction "D3_8") (pintype "passive"))
    )
    (net (code "59") (name "Net-(D512-K)") (class "Default")
      (node (ref "D512") (pin "1") (pinfunction "K_1") (pintype "passive"))
      (node (ref "IC502") (pin "7") (pinfunction "D4_7") (pintype "passive"))
    )
    (net (code "60") (name "Net-(IC500-RSET)") (class "Default")
      (node (ref "IC500") (pin "3") (pinfunction "RSET_3") (pintype "passive"))
      (node (ref "R500") (pin "1") (pinfunction "1_1") (pintype "passive"))
    )
    (net (code "61") (name "Net-(IC501-TEST1)") (class "Default")
      (node (ref "IC501") (pin "13") (pinfunction "TEST1_13") (pintype "passive"))
      (node (ref "R507") (pin "1") (pinfunction "1_1") (pintype "passive"))
    )
    (net (code "62") (name "Net-(IC501-TEST2)") (class "Default")
      (node (ref "IC501") (pin "17") (pinfunction "TEST2_17") (pintype "passive"))
      (node (ref "R508") (pin "1") (pinfunction "1_1") (pintype "passive"))
    )
    (net (code "63") (name "Net-(IC502-RSET)") (class "Default")
      (node (ref "IC502") (pin "3") (pinfunction "RSET_3") (pintype "passive"))
      (node (ref "R503") (pin "1") (pinfunction "1_1") (pintype "passive"))
    )
    (net (code "64") (name "Net-(IC503-CS-Pad5)") (class "Default")
      (node (ref "IC503") (pin "5") (pinfunction "CS_5") (pintype "passive"))
      (node (ref "IC503") (pin "6") (pinfunction "CS_6") (pintype "passive"))
      (node (ref "R506") (pin "1") (pinfunction "1_1") (pintype "passive"))
    )
    (net (code "65") (name "Net-(IC503-LED)") (class "Default")
      (node (ref "D513") (pin "K") (pinfunction "K_K") (pintype "passive"))
      (node (ref "IC503") (pin "4") (pinfunction "LED_4") (pintype "passive"))
      (node (ref "TP516") (pin "1") (pinfunction "TP_1") (pintype "passive"))
    )
    (net (code "66") (name "Net-(IC504-CS-Pad5)") (class "Default")
      (node (ref "IC504") (pin "5") (pinfunction "CS_5") (pintype "passive"))
      (node (ref "IC504") (pin "6") (pinfunction "CS_6") (pintype "passive"))
      (node (ref "R509") (pin "1") (pinfunction "1_1") (pintype "passive"))
    )
    (net (code "67") (name "Net-(IC504-LED)") (class "Default")
      (node (ref "D514") (pin "K") (pinfunction "K_K") (pintype "passive"))
      (node (ref "IC504") (pin "4") (pinfunction "LED_4") (pintype "passive"))
      (node (ref "TP520") (pin "1") (pinfunction "TP_1") (pintype "passive"))
    )
    (net (code "68") (name "Net-(IC505-CS-Pad5)") (class "Default")
      (node (ref "IC505") (pin "5") (pinfunction "CS_5") (pintype "passive"))
      (node (ref "IC505") (pin "6") (pinfunction "CS_6") (pintype "passive"))
      (node (ref "R510") (pin "1") (pinfunction "1_1") (pintype "passive"))
    )
    (net (code "69") (name "Net-(IC505-LED)") (class "Default")
      (node (ref "D515") (pin "K") (pinfunction "K_K") (pintype "passive"))
      (node (ref "IC505") (pin "4") (pinfunction "LED_4") (pintype "passive"))
      (node (ref "TP521") (pin "1") (pinfunction "TP_1") (pintype "passive"))
    )
    (net (code "70") (name "Net-(R500-Pad2)") (class "Default")
      (node (ref "R500") (pin "2") (pinfunction "2_2") (pintype "passive"))
      (node (ref "R501") (pin "2") (pinfunction "2_2") (pintype "passive"))
    )
    (net (code "71") (name "Net-(R503-Pad2)") (class "Default")
      (node (ref "R503") (pin "2") (pinfunction "2_2") (pintype "passive"))
      (node (ref "R504") (pin "2") (pinfunction "2_2") (pintype "passive"))
    )
    (net (code "72") (name "VBAT_LCD") (class "Default")
      (node (ref "D500") (pin "2") (pinfunction "A_2") (pintype "passive"))
      (node (ref "D501") (pin "2") (pinfunction "A_2") (pintype "passive"))
      (node (ref "D502") (pin "2") (pinfunction "A_2") (pintype "passive"))
      (node (ref "D503") (pin "2") (pinfunction "A_2") (pintype "passive"))
      (node (ref "D509") (pin "2") (pinfunction "A_2") (pintype "passive"))
      (node (ref "D510") (pin "2") (pinfunction "A_2") (pintype "passive"))
      (node (ref "D511") (pin "2") (pinfunction "A_2") (pintype "passive"))
      (node (ref "D512") (pin "2") (pinfunction "A_2") (pintype "passive"))
      (node (ref "J500") (pin "5") (pinfunction "5_5") (pintype "passive"))
      (node (ref "TP505") (pin "1") (pinfunction "TP_1") (pintype "passive"))
    )
    (net (code "73") (name "VLED_LCD") (class "Default")
      (node (ref "D513") (pin "A") (pinfunction "A_A") (pintype "passive"))
      (node (ref "D514") (pin "A") (pinfunction "A_A") (pintype "passive"))
      (node (ref "D515") (pin "A") (pinfunction "A_A") (pintype "passive"))
      (node (ref "J500") (pin "1") (pinfunction "1_1") (pintype "passive"))
      (node (ref "J500") (pin "2") (pinfunction "2_2") (pintype "passive"))
      (node (ref "J500") (pin "3") (pinfunction "3_3") (pintype "passive"))
      (node (ref "J500") (pin "4") (pinfunction "4_4") (pintype "passive"))
    )
    (net (code "74") (name "unconnected-(DS500-N.C.-Pad2)") (class "Default")
      (node (ref "DS500") (pin "2") (pinfunction "N.C._2") (pintype "passive"))
    )
    (net (code "75") (name "unconnected-(DS500-N.C.-Pad3)") (class "Default")
      (node (ref "DS500") (pin "3") (pinfunction "N.C._3") (pintype "passive"))
    )
    (net (code "76") (name "unconnected-(DS500-N.C.-Pad4)") (class "Default")
      (node (ref "DS500") (pin "4") (pinfunction "N.C._4") (pintype "passive"))
    )
    (net (code "77") (name "unconnected-(DS500-N.C.-Pad33)") (class "Default")
      (node (ref "DS500") (pin "33") (pinfunction "N.C._33") (pintype "passive"))
    )
    (net (code "78") (name "unconnected-(DS500-N.C.-Pad38)") (class "Default")
      (node (ref "DS500") (pin "38") (pinfunction "N.C._38") (pintype "passive"))
    )
    (net (code "79") (name "unconnected-(DS500-N.C.-Pad39)") (class "Default")
      (node (ref "DS500") (pin "39") (pinfunction "N.C._39") (pintype "passive"))
    )
    (net (code "80") (name "unconnected-(IC501-COM1-Pad7)") (class "Default")
      (node (ref "IC501") (pin "7") (pinfunction "COM1_7") (pintype "passive"))
    )
    (net (code "81") (name "unconnected-(IC501-COM2-Pad8)") (class "Default")
      (node (ref "IC501") (pin "8") (pinfunction "COM2_8") (pintype "passive"))
    )
    (net (code "82") (name "unconnected-(IC501-COM3-Pad9)") (class "Default")
      (node (ref "IC501") (pin "9") (pinfunction "COM3_9") (pintype "passive"))
    )
    (net (code "83") (name "unconnected-(IC501-SEG32-Pad2)") (class "Default")
      (node (ref "IC501") (pin "2") (pinfunction "SEG32_2") (pintype "passive"))
    )
    (net (code "84") (name "unconnected-(IC501-SEG33-Pad3)") (class "Default")
      (node (ref "IC501") (pin "3") (pinfunction "SEG33_3") (pintype "passive"))
    )
    (net (code "85") (name "unconnected-(IC501-SEG34-Pad4)") (class "Default")
      (node (ref "IC501") (pin "4") (pinfunction "SEG34_4") (pintype "passive"))
    )
    (net (code "86") (name "unconnected-(IC501-SEG35-Pad5)") (class "Default")
      (node (ref "IC501") (pin "5") (pinfunction "SEG35_5") (pintype "passive"))
    )
    (net (code "87") (name "unconnected-(IC503-NC-Pad3)") (class "Default")
      (node (ref "IC503") (pin "3") (pinfunction "NC_3") (pintype "passive+no_connect"))
    )
    (net (code "88") (name "unconnected-(IC503-NC-Pad7)") (class "Default")
      (node (ref "IC503") (pin "7") (pinfunction "NC_7") (pintype "passive+no_connect"))
    )
    (net (code "89") (name "unconnected-(IC504-NC-Pad3)") (class "Default")
      (node (ref "IC504") (pin "3") (pinfunction "NC_3") (pintype "passive+no_connect"))
    )
    (net (code "90") (name "unconnected-(IC504-NC-Pad7)") (class "Default")
      (node (ref "IC504") (pin "7") (pinfunction "NC_7") (pintype "passive+no_connect"))
    )
    (net (code "91") (name "unconnected-(IC505-NC-Pad3)") (class "Default")
      (node (ref "IC505") (pin "3") (pinfunction "NC_3") (pintype "passive+no_connect"))
    )
    (net (code "92") (name "unconnected-(IC505-NC-Pad7)") (class "Default")
      (node (ref "IC505") (pin "7") (pinfunction "NC_7") (pintype "passive+no_connect"))
    )
    (net (code "93") (name "unconnected-(SW500-Pad2)") (class "Default")
      (node (ref "SW500") (pin "2") (pinfunction "2_2") (pintype "passive"))
    )
    (net (code "94") (name "unconnected-(SW500-Pad3)") (class "Default")
      (node (ref "SW500") (pin "3") (pinfunction "3_3") (pintype "passive"))
    )
    (net (code "95") (name "unconnected-(SW501-Pad2)") (class "Default")
      (node (ref "SW501") (pin "2") (pinfunction "2_2") (pintype "passive"))
    )
    (net (code "96") (name "unconnected-(SW501-Pad3)") (class "Default")
      (node (ref "SW501") (pin "3") (pinfunction "3_3") (pintype "passive"))
    )
    (net (code "97") (name "unconnected-(SW502-Pad2)") (class "Default")
      (node (ref "SW502") (pin "2") (pinfunction "2_2") (pintype "passive"))
    )
    (net (code "98") (name "unconnected-(SW502-Pad3)") (class "Default")
      (node (ref "SW502") (pin "3") (pinfunction "3_3") (pintype "passive"))
    )
    (net (code "99") (name "unconnected-(SW503-Pad2)") (class "Default")
      (node (ref "SW503") (pin "2") (pinfunction "2_2") (pintype "passive"))
    )
    (net (code "100") (name "unconnected-(SW503-Pad3)") (class "Default")
      (node (ref "SW503") (pin "3") (pinfunction "3_3") (pintype "passive"))
    )
    (net (code "101") (name "unconnected-(SW504-Pad2)") (class "Default")
      (node (ref "SW504") (pin "2") (pinfunction "2_2") (pintype "passive"))
    )
    (net (code "102") (name "unconnected-(SW504-Pad3)") (class "Default")
      (node (ref "SW504") (pin "3") (pinfunction "3_3") (pintype "passive"))
    )
  )
)
